# v1_3.net
KiCad netlist of a schematic drawn in EAGLE
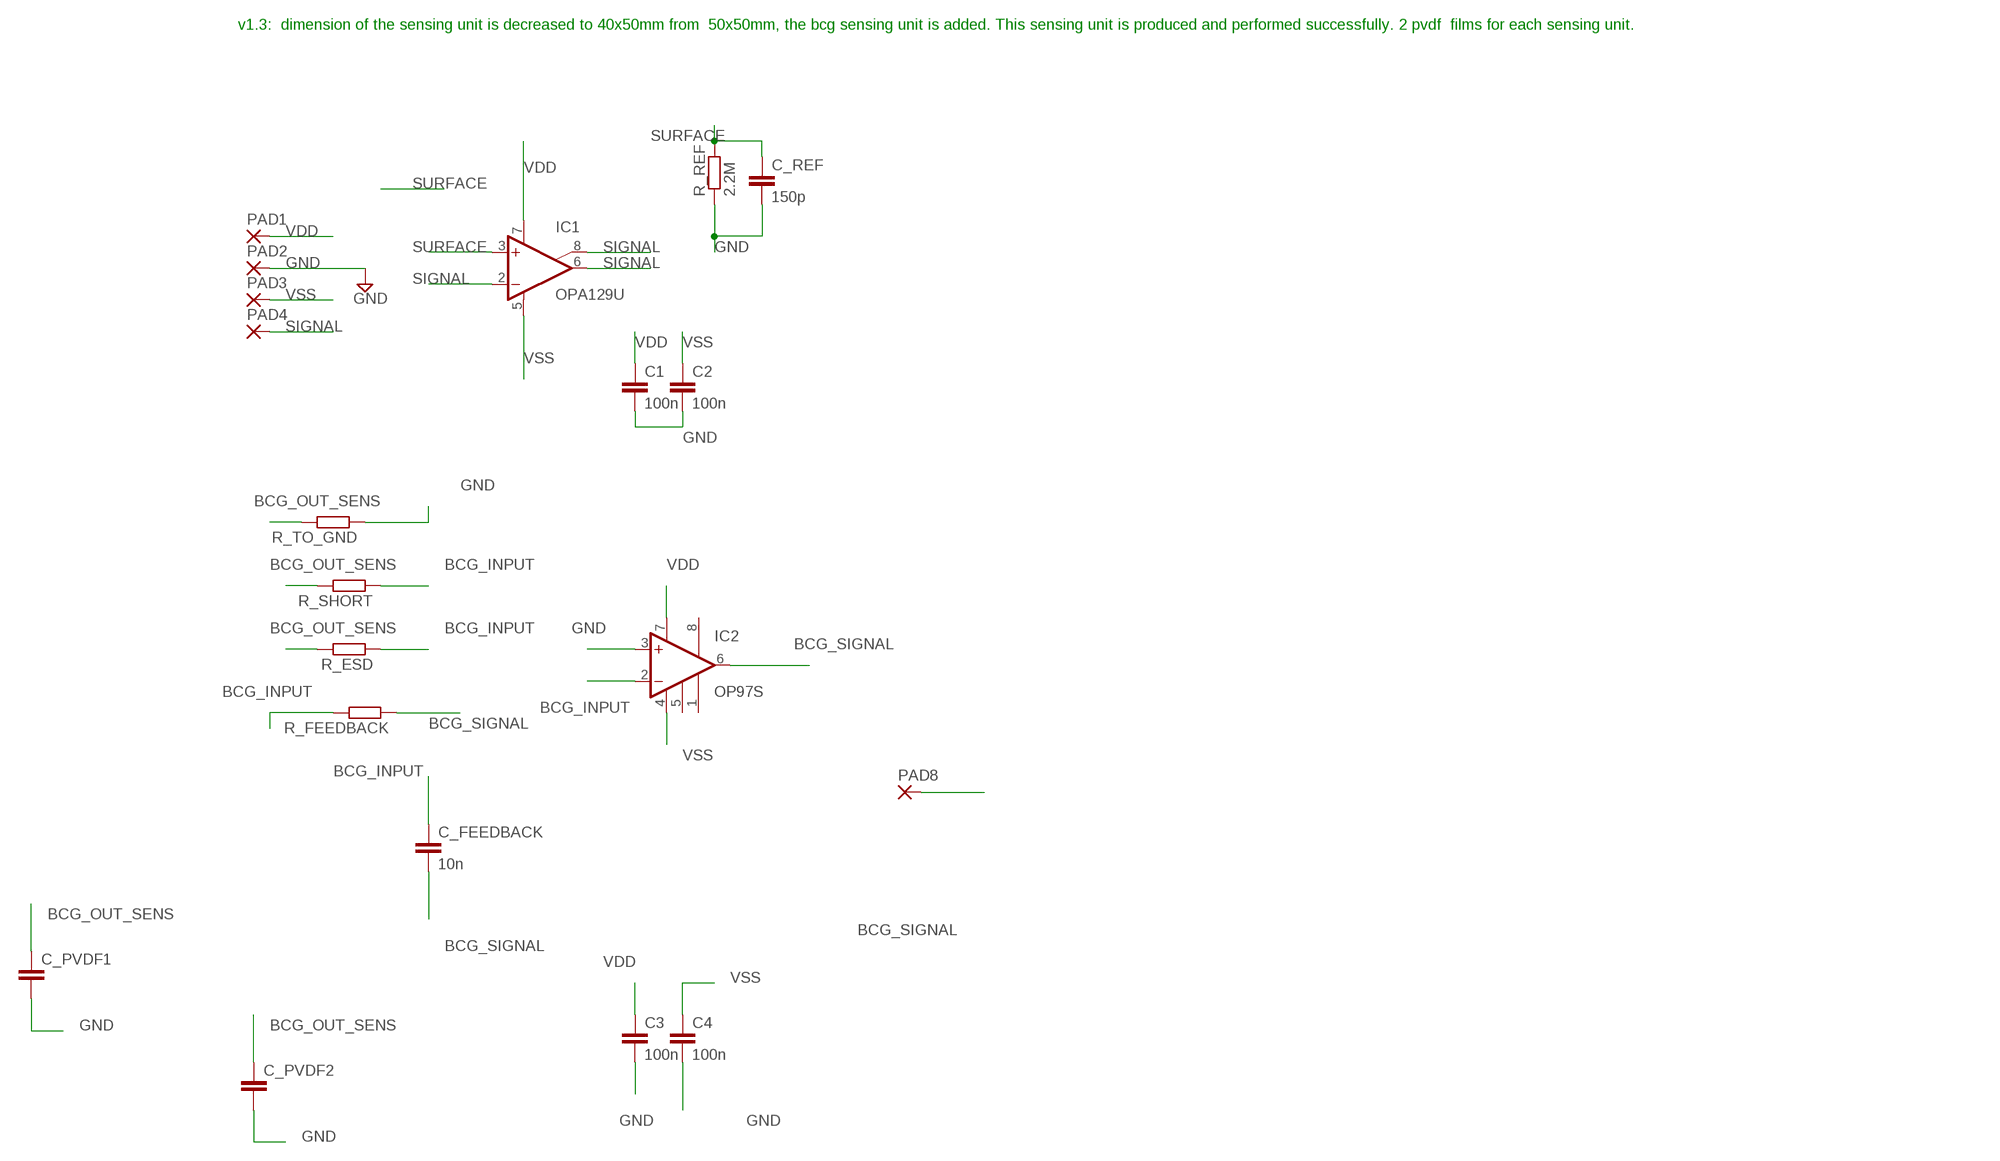
[diagram p0: schematic, sheet 1]

(export (version "E")
  (design (tool "Eeschema 10.0.6"))
  (components
    (comp (ref "C1")
      (value "100n")
      (footprint "eagle-import:C0805")
      (libsource (lib "eagle-import") (part "resistor_C-EUC0805"))
    )
    (comp (ref "C2")
      (value "100n")
      (footprint "eagle-import:C0805")
      (libsource (lib "eagle-import") (part "resistor_C-EUC0805"))
    )
    (comp (ref "C3")
      (value "100n")
      (footprint "eagle-import:C0805")
      (libsource (lib "eagle-import") (part "resistor_C-EUC0805"))
    )
    (comp (ref "C4")
      (value "100n")
      (footprint "eagle-import:C0805")
      (libsource (lib "eagle-import") (part "resistor_C-EUC0805"))
    )
    (comp (ref "C_FEEDBACK")
      (value "10n")
      (footprint "eagle-import:C0805")
      (libsource (lib "eagle-import") (part "C-EUC0805"))
    )
    (comp (ref "C_PVDF1")
      (value "C-EUC0805")
      (footprint "eagle-import:C0805")
      (libsource (lib "eagle-import") (part "C-EUC0805"))
    )
    (comp (ref "C_PVDF2")
      (value "C-EUC0805")
      (footprint "eagle-import:C0805")
      (libsource (lib "eagle-import") (part "C-EUC0805"))
    )
    (comp (ref "C_REF")
      (value "150p")
      (footprint "eagle-import:C0805")
      (libsource (lib "eagle-import") (part "resistor_C-EUC0805"))
    )
    (comp (ref "IC1")
      (value "OPA129U")
      (footprint "eagle-import:SO08")
      (fields (field (name "MF") "TEXAS INSTRUMENTS"))
      (libsource (lib "eagle-import") (part "OPA129U"))
    )
    (comp (ref "IC2")
      (value "OP97S")
      (footprint "eagle-import:SO08")
      (libsource (lib "eagle-import") (part "OP97S"))
    )
    (comp (ref "PAD1")
      (value "SMD5")
      (footprint "eagle-import:SMD2,54-5,08")
      (libsource (lib "eagle-import") (part "SMD5"))
    )
    (comp (ref "PAD2")
      (value "SMD5")
      (footprint "eagle-import:SMD2,54-5,08")
      (libsource (lib "eagle-import") (part "SMD5"))
    )
    (comp (ref "PAD3")
      (value "SMD5")
      (footprint "eagle-import:SMD2,54-5,08")
      (libsource (lib "eagle-import") (part "SMD5"))
    )
    (comp (ref "PAD4")
      (value "SMD5")
      (footprint "eagle-import:SMD2,54-5,08")
      (libsource (lib "eagle-import") (part "SMD5"))
    )
    (comp (ref "PAD8")
      (value "SMD5")
      (footprint "eagle-import:SMD2,54-5,08")
      (libsource (lib "eagle-import") (part "wirepad_412_SMD5"))
    )
    (comp (ref "R_ESD")
      (value "1M")
      (footprint "eagle-import:M0805")
      (libsource (lib "eagle-import") (part "rcl_334_R-EU_M0805"))
    )
    (comp (ref "R_FEEDBACK")
      (value "100M")
      (footprint "eagle-import:M0805")
      (libsource (lib "eagle-import") (part "rcl_334_R-EU_M0805"))
    )
    (comp (ref "R_REF")
      (value "2.2M")
      (footprint "eagle-import:M0805")
      (libsource (lib "eagle-import") (part "R-EU_M0805"))
    )
    (comp (ref "R_SHORT")
      (value "1M")
      (footprint "eagle-import:M0805")
      (libsource (lib "eagle-import") (part "rcl_334_R-EU_M0805"))
    )
    (comp (ref "R_TO_GND")
      (value "1M")
      (footprint "eagle-import:M0805")
      (libsource (lib "eagle-import") (part "rcl_334_R-EU_M0805"))
    )
  )
  (nets
    (net (code "1") (name "/BCG_INPUT") (class "Default")
      (node (ref "C_FEEDBACK") (pin "1") (pinfunction "1_1") (pintype "passive"))
      (node (ref "IC2") (pin "2") (pinfunction "-IN_2") (pintype "input"))
      (node (ref "R_ESD") (pin "1") (pinfunction "1_1") (pintype "passive"))
      (node (ref "R_FEEDBACK") (pin "2") (pinfunction "2_2") (pintype "passive"))
      (node (ref "R_SHORT") (pin "1") (pinfunction "1_1") (pintype "passive"))
    )
    (net (code "2") (name "/BCG_OUT_SENS") (class "Default")
      (node (ref "C_PVDF1") (pin "1") (pinfunction "1_1") (pintype "passive"))
      (node (ref "C_PVDF2") (pin "1") (pinfunction "1_1") (pintype "passive"))
      (node (ref "R_ESD") (pin "2") (pinfunction "2_2") (pintype "passive"))
      (node (ref "R_SHORT") (pin "2") (pinfunction "2_2") (pintype "passive"))
      (node (ref "R_TO_GND") (pin "2") (pinfunction "2_2") (pintype "passive"))
    )
    (net (code "3") (name "/BCG_SIGNAL") (class "Default")
      (node (ref "C_FEEDBACK") (pin "2") (pinfunction "2_2") (pintype "passive"))
      (node (ref "IC2") (pin "6") (pinfunction "OUT_6") (pintype "output"))
      (node (ref "PAD8") (pin "1") (pinfunction "P_1") (pintype "passive"))
      (node (ref "R_FEEDBACK") (pin "1") (pinfunction "1_1") (pintype "passive"))
    )
    (net (code "4") (name "/SIGNAL") (class "Default")
      (node (ref "IC1") (pin "2") (pinfunction "-IN_2") (pintype "input"))
      (node (ref "IC1") (pin "6") (pinfunction "OUT_6") (pintype "output"))
      (node (ref "IC1") (pin "8") (pinfunction "SUBS_8") (pintype "passive"))
      (node (ref "PAD4") (pin "1") (pinfunction "P_1") (pintype "passive"))
    )
    (net (code "5") (name "/SURFACE") (class "Default")
      (node (ref "C_REF") (pin "1") (pinfunction "1_1") (pintype "passive"))
      (node (ref "IC1") (pin "3") (pinfunction "+IN_3") (pintype "input"))
      (node (ref "R_REF") (pin "2") (pinfunction "2_2") (pintype "passive"))
    )
    (net (code "6") (name "/VDD") (class "Default")
      (node (ref "C1") (pin "1") (pinfunction "1_1") (pintype "passive"))
      (node (ref "C3") (pin "1") (pinfunction "1_1") (pintype "passive"))
      (node (ref "IC1") (pin "7") (pinfunction "V+_7") (pintype "power_in"))
      (node (ref "IC2") (pin "7") (pinfunction "V+_7") (pintype "power_in"))
      (node (ref "PAD1") (pin "1") (pinfunction "P_1") (pintype "passive"))
    )
    (net (code "7") (name "/VSS") (class "Default")
      (node (ref "C2") (pin "1") (pinfunction "1_1") (pintype "passive"))
      (node (ref "C4") (pin "1") (pinfunction "1_1") (pintype "passive"))
      (node (ref "IC1") (pin "5") (pinfunction "V-_5") (pintype "power_in"))
      (node (ref "IC2") (pin "4") (pinfunction "V-_4") (pintype "power_in"))
      (node (ref "PAD3") (pin "1") (pinfunction "P_1") (pintype "passive"))
    )
    (net (code "8") (name "GND") (class "Default")
      (node (ref "C1") (pin "2") (pinfunction "2_2") (pintype "passive"))
      (node (ref "C2") (pin "2") (pinfunction "2_2") (pintype "passive"))
      (node (ref "C3") (pin "2") (pinfunction "2_2") (pintype "passive"))
      (node (ref "C4") (pin "2") (pinfunction "2_2") (pintype "passive"))
      (node (ref "C_PVDF1") (pin "2") (pinfunction "2_2") (pintype "passive"))
      (node (ref "C_PVDF2") (pin "2") (pinfunction "2_2") (pintype "passive"))
      (node (ref "C_REF") (pin "2") (pinfunction "2_2") (pintype "passive"))
      (node (ref "IC2") (pin "3") (pinfunction "+IN_3") (pintype "input"))
      (node (ref "PAD2") (pin "1") (pinfunction "P_1") (pintype "passive"))
      (node (ref "R_REF") (pin "1") (pinfunction "1_1") (pintype "passive"))
      (node (ref "R_TO_GND") (pin "1") (pinfunction "1_1") (pintype "passive"))
    )
    (net (code "9") (name "unconnected-(IC2-BAL1-Pad1)") (class "Default")
      (node (ref "IC2") (pin "1") (pinfunction "BAL1_1") (pintype "passive"))
    )
    (net (code "10") (name "unconnected-(IC2-BAL2-Pad8)") (class "Default")
      (node (ref "IC2") (pin "8") (pinfunction "BAL2_8") (pintype "passive"))
    )
    (net (code "11") (name "unconnected-(IC2-COMP-Pad5)") (class "Default")
      (node (ref "IC2") (pin "5") (pinfunction "COMP_5") (pintype "passive"))
    )
  )
)
